# BuckPower.net
KiCad netlist of a schematic drawn in EAGLE
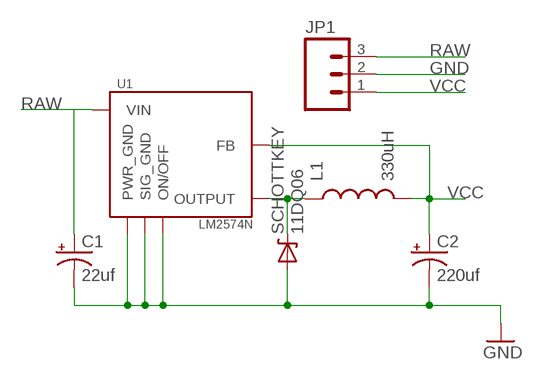
[diagram p0: schematic, sheet 1]

(export (version "E")
  (design (tool "Eeschema 10.0.6"))
  (components
    (comp (ref "C1")
      (value "22uf")
      (footprint "eagle-import:CPOL-RADIAL-100UF-25V")
      (libsource (lib "eagle-import") (part "CAP_POLPTH1"))
    )
    (comp (ref "C2")
      (value "220uf")
      (footprint "eagle-import:CPOL-RADIAL-100UF-25V")
      (libsource (lib "eagle-import") (part "CAP_POLPTH1"))
    )
    (comp (ref "JP1")
      (value "M031X03_NO_SILK")
      (footprint "eagle-import:1X03_NO_SILK")
      (libsource (lib "eagle-import") (part "M031X03_NO_SILK"))
    )
    (comp (ref "L1")
      (value "330uH")
      (footprint "eagle-import:INDUCTOR-1206")
      (libsource (lib "eagle-import") (part "INDUCTORH1206"))
    )
    (comp (ref "SCHOTTKEY")
      (value "11DQ06")
      (footprint "eagle-import:DIODE-ZENER")
      (libsource (lib "eagle-import") (part "DIODE-ZENERPTH"))
    )
    (comp (ref "U1")
      (value "LM2574N")
      (footprint "eagle-import:8DILL")
      (libsource (lib "eagle-import") (part "LM2574N"))
    )
  )
  (nets
    (net (code "1") (name "/RAW") (class "Default")
      (node (ref "C1") (pin "1") (pinfunction "+_1") (pintype "passive"))
      (node (ref "JP1") (pin "3") (pinfunction "3_3") (pintype "passive"))
      (node (ref "U1") (pin "5") (pinfunction "VIN_5") (pintype "bidirectional"))
    )
    (net (code "2") (name "/VCC") (class "Default")
      (node (ref "C2") (pin "1") (pinfunction "+_1") (pintype "passive"))
      (node (ref "JP1") (pin "1") (pinfunction "1_1") (pintype "passive"))
      (node (ref "L1") (pin "P$2") (pinfunction "2_P$2") (pintype "passive"))
      (node (ref "U1") (pin "1") (pinfunction "FB_1") (pintype "bidirectional"))
    )
    (net (code "3") (name "GND") (class "Default")
      (node (ref "C1") (pin "2") (pinfunction "-_2") (pintype "passive"))
      (node (ref "C2") (pin "2") (pinfunction "-_2") (pintype "passive"))
      (node (ref "JP1") (pin "2") (pinfunction "2_2") (pintype "passive"))
      (node (ref "SCHOTTKEY") (pin "P$2") (pinfunction "A_P$2") (pintype "passive"))
      (node (ref "U1") (pin "2") (pinfunction "SIG_GND_2") (pintype "bidirectional"))
      (node (ref "U1") (pin "3") (pinfunction "ON/OFF_3") (pintype "bidirectional"))
      (node (ref "U1") (pin "4") (pinfunction "PWR_GND_4") (pintype "bidirectional"))
    )
    (net (code "4") (name "Net-(L1-1)") (class "Default")
      (node (ref "L1") (pin "P$1") (pinfunction "1_P$1") (pintype "passive"))
      (node (ref "SCHOTTKEY") (pin "P$1") (pinfunction "C_P$1") (pintype "passive"))
      (node (ref "U1") (pin "7") (pinfunction "OUTPUT_7") (pintype "bidirectional"))
    )
  )
)
